# 03_GYROSCOPE.net
KiCad netlist of a schematic drawn in Altium Designer
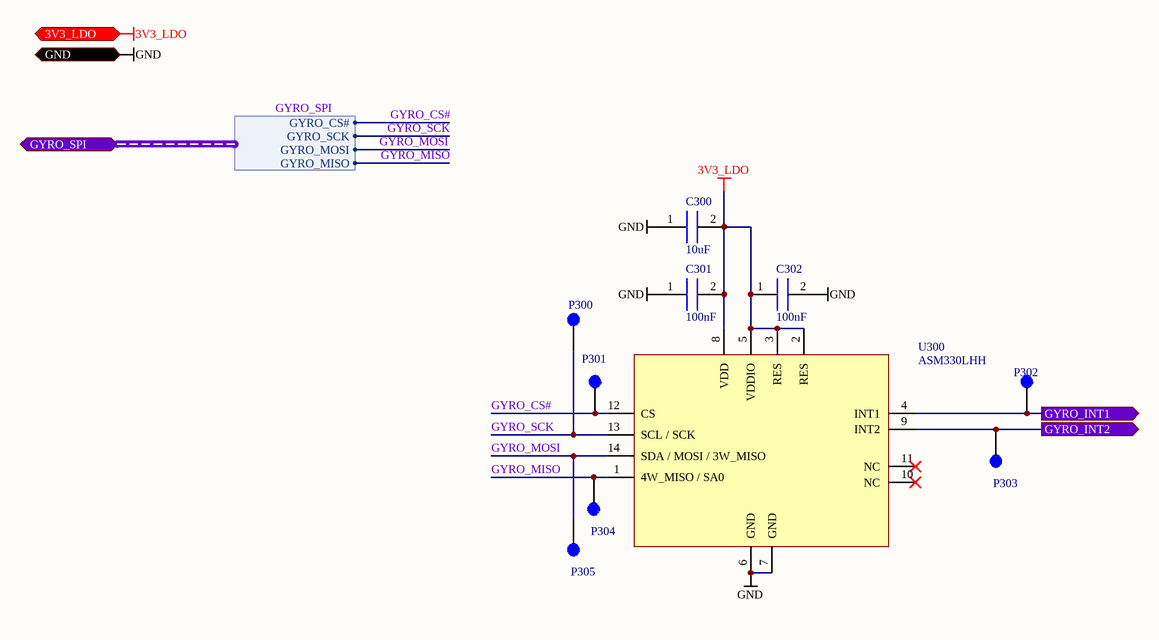
[diagram p0: 03_GYROSCOPE.SchDoc]

(export (version "E")
  (design (tool "Eeschema 10.0.6"))
  (components
    (comp (ref "C300")
      (value "10uF")
      (footprint "CAP_0402")
      (description "CAPACITOR 10uF 20% 6.3V 0402 GRM155R60J106ME05D")
      (fields (field (name "TOLERANCE") "20%") (field (name "MANUFACTURER") "MURATA"))
      (libsource (lib "Capacitors") (part "10uF 20% 6.3V 0402 GRM155R60J106ME05D"))
    )
    (comp (ref "C301")
      (value "100nF")
      (footprint "CAP_0402")
      (description "CAPACITOR 100nF 10% X7R 0402")
      (fields (field (name "TOLERANCE") "10%") (field (name "MANUFACTURER") "MURATA"))
      (libsource (lib "Capacitors") (part "100nF_10%_16V_0402_GRM155R71C104KA88J"))
    )
    (comp (ref "C302")
      (value "100nF")
      (footprint "CAP_0402")
      (description "CAPACITOR 100nF 10% X7R 0402")
      (fields (field (name "TOLERANCE") "10%") (field (name "MANUFACTURER") "MURATA"))
      (libsource (lib "Capacitors") (part "100nF_10%_16V_0402_GRM155R71C104KA88J"))
    )
    (comp (ref "P300")
      (value "TEST_POINT_2mm")
      (footprint "TEST_POINT_2mm")
      (libsource (lib "Connectors") (part "TEST_POINT_2mm"))
    )
    (comp (ref "P301")
      (value "TEST_POINT_2mm")
      (footprint "TEST_POINT_2mm")
      (libsource (lib "Connectors") (part "TEST_POINT_2mm"))
    )
    (comp (ref "P302")
      (value "TEST_POINT_2mm")
      (footprint "TEST_POINT_2mm")
      (libsource (lib "Connectors") (part "TEST_POINT_2mm"))
    )
    (comp (ref "P303")
      (value "TEST_POINT_2mm")
      (footprint "TEST_POINT_2mm")
      (libsource (lib "Connectors") (part "TEST_POINT_2mm"))
    )
    (comp (ref "P304")
      (value "TEST_POINT_2mm")
      (footprint "TEST_POINT_2mm")
      (libsource (lib "Connectors") (part "TEST_POINT_2mm"))
    )
    (comp (ref "P305")
      (value "TEST_POINT_2mm")
      (footprint "TEST_POINT_2mm")
      (libsource (lib "Connectors") (part "TEST_POINT_2mm"))
    )
    (comp (ref "U300")
      (value "GYRO_3D_3.6V_ACEL_ASM330LHH")
      (footprint "LGA14")
      (description "Gyroscope and accelerometer 3D 3.6V ASM330LHH")
      (fields (field (name "MANUFACTURER") "ST") (field (name "MANUFACTURER REFERENCE") "ASM330LHH"))
      (libsource (lib "Semiconductor") (part "GYRO_3D_3.6V_ACEL_ASM330LHH"))
    )
  )
  (nets
    (net (code "2") (name "/GYRO_CS#") (class "Default")
      (node (ref "P301") (pin "1") (pinfunction "1_1") (pintype "passive"))
      (node (ref "U300") (pin "12") (pinfunction "CS_12") (pintype "passive"))
    )
    (net (code "3") (name "/GYRO_INT1") (class "Default")
      (node (ref "P302") (pin "1") (pinfunction "1_1") (pintype "passive"))
      (node (ref "U300") (pin "4") (pinfunction "INT1_4") (pintype "passive"))
    )
    (net (code "4") (name "/GYRO_INT2") (class "Default")
      (node (ref "P303") (pin "1") (pinfunction "1_1") (pintype "passive"))
      (node (ref "U300") (pin "9") (pinfunction "INT2_9") (pintype "passive"))
    )
    (net (code "5") (name "/GYRO_MISO") (class "Default")
      (node (ref "P304") (pin "1") (pinfunction "1_1") (pintype "passive"))
      (node (ref "U300") (pin "1") (pinfunction "4W_MISO_/_SA0_1") (pintype "passive"))
    )
    (net (code "6") (name "/GYRO_MOSI") (class "Default")
      (node (ref "P305") (pin "1") (pinfunction "1_1") (pintype "passive"))
      (node (ref "U300") (pin "14") (pinfunction "SDA_/_MOSI_/_3W_MISO_14") (pintype "passive"))
    )
    (net (code "7") (name "/GYRO_SCK") (class "Default")
      (node (ref "P300") (pin "1") (pinfunction "1_1") (pintype "passive"))
      (node (ref "U300") (pin "13") (pinfunction "SCL_/_SCK_13") (pintype "passive"))
    )
    (net (code "9") (name "3V3_LDO") (class "Default")
      (node (ref "C300") (pin "2") (pinfunction "2_2") (pintype "passive"))
      (node (ref "C301") (pin "2") (pinfunction "2_2") (pintype "passive"))
      (node (ref "C302") (pin "1") (pinfunction "1_1") (pintype "passive"))
      (node (ref "U300") (pin "2") (pinfunction "RES_2") (pintype "passive"))
      (node (ref "U300") (pin "3") (pinfunction "RES_3") (pintype "passive"))
      (node (ref "U300") (pin "5") (pinfunction "VDDIO_5") (pintype "passive"))
      (node (ref "U300") (pin "8") (pinfunction "VDD_8") (pintype "passive"))
    )
    (net (code "10") (name "GND") (class "Default")
      (node (ref "C300") (pin "1") (pinfunction "1_1") (pintype "passive"))
      (node (ref "C301") (pin "1") (pinfunction "1_1") (pintype "passive"))
      (node (ref "C302") (pin "2") (pinfunction "2_2") (pintype "passive"))
      (node (ref "U300") (pin "6") (pinfunction "GND_6") (pintype "passive"))
      (node (ref "U300") (pin "7") (pinfunction "GND_7") (pintype "passive"))
    )
    (net (code "11") (name "unconnected-(U300-NC-Pad10)") (class "Default")
      (node (ref "U300") (pin "10") (pinfunction "NC_10") (pintype "passive+no_connect"))
    )
    (net (code "12") (name "unconnected-(U300-NC-Pad11)") (class "Default")
      (node (ref "U300") (pin "11") (pinfunction "NC_11") (pintype "passive+no_connect"))
    )
  )
)
